# LCD_boardv2.net
KiCad netlist of a schematic drawn in EAGLE
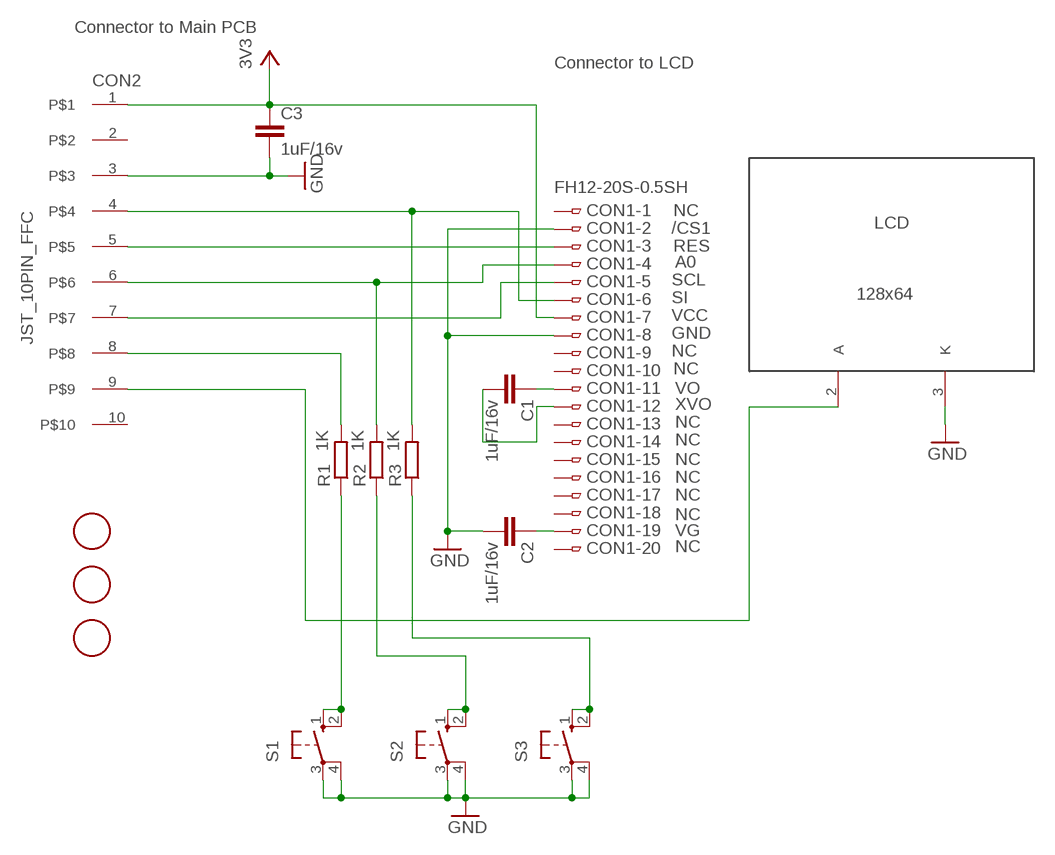
[diagram p0: schematic, sheet 1]

(export (version "E")
  (design (tool "Eeschema 10.0.6"))
  (components
    (comp (ref "C1")
      (value "1uF/16v")
      (footprint "eagle-import:C0805")
      (libsource (lib "eagle-import") (part "C-EUC0805"))
    )
    (comp (ref "C2")
      (value "1uF/16v")
      (footprint "eagle-import:C0805")
      (libsource (lib "eagle-import") (part "C-EUC0805"))
    )
    (comp (ref "C3")
      (value "1uF/16v")
      (footprint "eagle-import:C0805")
      (libsource (lib "eagle-import") (part "C-EUC0805"))
    )
    (comp (ref "CON1")
      (value "FH12-20S-0.5SH")
      (footprint "eagle-import:FH12-20S-0.5SH")
      (fields (field (name "MPN") "FH12-20S-0.5SH(55)"))
      (libsource (lib "eagle-import") (part "FH12-20S-0.5SH"))
    )
    (comp (ref "CON2")
      (value "JST_10PIN_FFC")
      (footprint "eagle-import:JST_10PIN_FFC")
      (libsource (lib "eagle-import") (part "JST_10PIN_FFC"))
    )
    (comp (ref "R1")
      (value "1K")
      (footprint "eagle-import:R0603")
      (libsource (lib "eagle-import") (part "R-EU_R0603"))
    )
    (comp (ref "R2")
      (value "1K")
      (footprint "eagle-import:R0603")
      (libsource (lib "eagle-import") (part "R-EU_R0603"))
    )
    (comp (ref "R3")
      (value "1K")
      (footprint "eagle-import:R0603")
      (libsource (lib "eagle-import") (part "R-EU_R0603"))
    )
    (comp (ref "S1")
      (value "10-XX")
      (footprint "eagle-import:B3F-10XX")
      (fields (field (name "MPN") "B3F-1000"))
      (libsource (lib "eagle-import") (part "10-XX"))
    )
    (comp (ref "S2")
      (value "10-XX")
      (footprint "eagle-import:B3F-10XX")
      (fields (field (name "MPN") "B3F-1000"))
      (libsource (lib "eagle-import") (part "10-XX"))
    )
    (comp (ref "S3")
      (value "10-XX")
      (footprint "eagle-import:B3F-10XX")
      (fields (field (name "MPN") "B3F-1000"))
      (libsource (lib "eagle-import") (part "10-XX"))
    )
    (comp (ref "U$1")
      (value "LCD_DEM128064")
      (footprint "eagle-import:LCD_DEM128064")
      (libsource (lib "eagle-import") (part "LCD_DEM128064"))
    )
    (comp (ref "U$2")
      (value "FIDUCIAL")
      (footprint "eagle-import:FIDUCIAL_1MM")
      (libsource (lib "eagle-import") (part "FIDUCIAL"))
    )
    (comp (ref "U$3")
      (value "FIDUCIAL")
      (footprint "eagle-import:FIDUCIAL_1MM")
      (libsource (lib "eagle-import") (part "FIDUCIAL"))
    )
    (comp (ref "U$4")
      (value "FIDUCIAL")
      (footprint "eagle-import:FIDUCIAL_1MM")
      (libsource (lib "eagle-import") (part "FIDUCIAL"))
    )
  )
  (nets
    (net (code "1") (name "3V3") (class "Default")
      (node (ref "C3") (pin "1") (pinfunction "1_1") (pintype "passive"))
      (node (ref "CON1") (pin "7") (pinfunction "1_7") (pintype "passive"))
      (node (ref "CON2") (pin "1") (pinfunction "P$1_1") (pintype "bidirectional"))
    )
    (net (code "2") (name "GND") (class "Default")
      (node (ref "C2") (pin "2") (pinfunction "2_2") (pintype "passive"))
      (node (ref "C3") (pin "2") (pinfunction "2_2") (pintype "passive"))
      (node (ref "CON1") (pin "2") (pinfunction "1_2") (pintype "passive"))
      (node (ref "CON1") (pin "8") (pinfunction "1_8") (pintype "passive"))
      (node (ref "CON2") (pin "3") (pinfunction "P$3_3") (pintype "bidirectional"))
      (node (ref "S1") (pin "3") (pinfunction "P_3") (pintype "passive"))
      (node (ref "S1") (pin "4") (pinfunction "P1_4") (pintype "passive"))
      (node (ref "S2") (pin "3") (pinfunction "P_3") (pintype "passive"))
      (node (ref "S2") (pin "4") (pinfunction "P1_4") (pintype "passive"))
      (node (ref "S3") (pin "3") (pinfunction "P_3") (pintype "passive"))
      (node (ref "S3") (pin "4") (pinfunction "P1_4") (pintype "passive"))
      (node (ref "U$1") (pin "3") (pinfunction "K_3") (pintype "bidirectional"))
    )
    (net (code "3") (name "Net-(CON1C-1)") (class "Default")
      (node (ref "C1") (pin "1") (pinfunction "1_1") (pintype "passive"))
      (node (ref "CON1") (pin "11") (pinfunction "1_11") (pintype "passive"))
    )
    (net (code "4") (name "Net-(CON1D-1)") (class "Default")
      (node (ref "C1") (pin "2") (pinfunction "2_2") (pintype "passive"))
      (node (ref "CON1") (pin "12") (pinfunction "1_12") (pintype "passive"))
    )
    (net (code "5") (name "Net-(CON1K-1)") (class "Default")
      (node (ref "C2") (pin "1") (pinfunction "1_1") (pintype "passive"))
      (node (ref "CON1") (pin "19") (pinfunction "1_19") (pintype "passive"))
    )
    (net (code "6") (name "Net-(CON1N-1)") (class "Default")
      (node (ref "CON1") (pin "3") (pinfunction "1_3") (pintype "passive"))
      (node (ref "CON2") (pin "5") (pinfunction "P$5_5") (pintype "bidirectional"))
    )
    (net (code "7") (name "Net-(CON1O-1)") (class "Default")
      (node (ref "CON1") (pin "4") (pinfunction "1_4") (pintype "passive"))
      (node (ref "CON2") (pin "6") (pinfunction "P$6_6") (pintype "bidirectional"))
      (node (ref "R2") (pin "2") (pinfunction "2_2") (pintype "passive"))
    )
    (net (code "8") (name "Net-(CON1P-1)") (class "Default")
      (node (ref "CON1") (pin "5") (pinfunction "1_5") (pintype "passive"))
      (node (ref "CON2") (pin "7") (pinfunction "P$7_7") (pintype "bidirectional"))
    )
    (net (code "9") (name "Net-(CON1Q-1)") (class "Default")
      (node (ref "CON1") (pin "6") (pinfunction "1_6") (pintype "passive"))
      (node (ref "CON2") (pin "4") (pinfunction "P$4_4") (pintype "bidirectional"))
      (node (ref "R3") (pin "2") (pinfunction "2_2") (pintype "passive"))
    )
    (net (code "10") (name "Net-(CON2-P$8)") (class "Default")
      (node (ref "CON2") (pin "8") (pinfunction "P$8_8") (pintype "bidirectional"))
      (node (ref "R1") (pin "2") (pinfunction "2_2") (pintype "passive"))
    )
    (net (code "11") (name "Net-(CON2-P$9)") (class "Default")
      (node (ref "CON2") (pin "9") (pinfunction "P$9_9") (pintype "bidirectional"))
      (node (ref "U$1") (pin "2") (pinfunction "A_2") (pintype "bidirectional"))
    )
    (net (code "12") (name "Net-(S1-S)") (class "Default")
      (node (ref "R1") (pin "1") (pinfunction "1_1") (pintype "passive"))
      (node (ref "S1") (pin "1") (pinfunction "S_1") (pintype "passive"))
      (node (ref "S1") (pin "2") (pinfunction "S1_2") (pintype "passive"))
    )
    (net (code "13") (name "Net-(S2-S)") (class "Default")
      (node (ref "R2") (pin "1") (pinfunction "1_1") (pintype "passive"))
      (node (ref "S2") (pin "1") (pinfunction "S_1") (pintype "passive"))
      (node (ref "S2") (pin "2") (pinfunction "S1_2") (pintype "passive"))
    )
    (net (code "14") (name "Net-(S3-S)") (class "Default")
      (node (ref "R3") (pin "1") (pinfunction "1_1") (pintype "passive"))
      (node (ref "S3") (pin "1") (pinfunction "S_1") (pintype "passive"))
      (node (ref "S3") (pin "2") (pinfunction "S1_2") (pintype "passive"))
    )
    (net (code "15") (name "unconnected-(CON1-Pad1)") (class "Default")
      (node (ref "CON1") (pin "1") (pinfunction "1_1") (pintype "passive"))
    )
    (net (code "16") (name "unconnected-(CON1B-1-Pad10)") (class "Default")
      (node (ref "CON1") (pin "10") (pinfunction "1_10") (pintype "passive"))
    )
    (net (code "17") (name "unconnected-(CON1E-1-Pad13)") (class "Default")
      (node (ref "CON1") (pin "13") (pinfunction "1_13") (pintype "passive"))
    )
    (net (code "18") (name "unconnected-(CON1F-1-Pad14)") (class "Default")
      (node (ref "CON1") (pin "14") (pinfunction "1_14") (pintype "passive"))
    )
    (net (code "19") (name "unconnected-(CON1G-1-Pad15)") (class "Default")
      (node (ref "CON1") (pin "15") (pinfunction "1_15") (pintype "passive"))
    )
    (net (code "20") (name "unconnected-(CON1H-1-Pad16)") (class "Default")
      (node (ref "CON1") (pin "16") (pinfunction "1_16") (pintype "passive"))
    )
    (net (code "21") (name "unconnected-(CON1I-1-Pad17)") (class "Default")
      (node (ref "CON1") (pin "17") (pinfunction "1_17") (pintype "passive"))
    )
    (net (code "22") (name "unconnected-(CON1J-1-Pad18)") (class "Default")
      (node (ref "CON1") (pin "18") (pinfunction "1_18") (pintype "passive"))
    )
    (net (code "23") (name "unconnected-(CON1M-1-Pad20)") (class "Default")
      (node (ref "CON1") (pin "20") (pinfunction "1_20") (pintype "passive"))
    )
    (net (code "24") (name "unconnected-(CON1T-1-Pad9)") (class "Default")
      (node (ref "CON1") (pin "9") (pinfunction "1_9") (pintype "passive"))
    )
    (net (code "25") (name "unconnected-(CON2-P$2-Pad2)") (class "Default")
      (node (ref "CON2") (pin "2") (pinfunction "P$2_2") (pintype "bidirectional"))
    )
    (net (code "26") (name "unconnected-(CON2-P$10-Pad10)") (class "Default")
      (node (ref "CON2") (pin "10") (pinfunction "P$10_10") (pintype "bidirectional"))
    )
  )
)
